# STM32_Microcontroller.net
KiCad netlist of a schematic drawn in Altium Designer
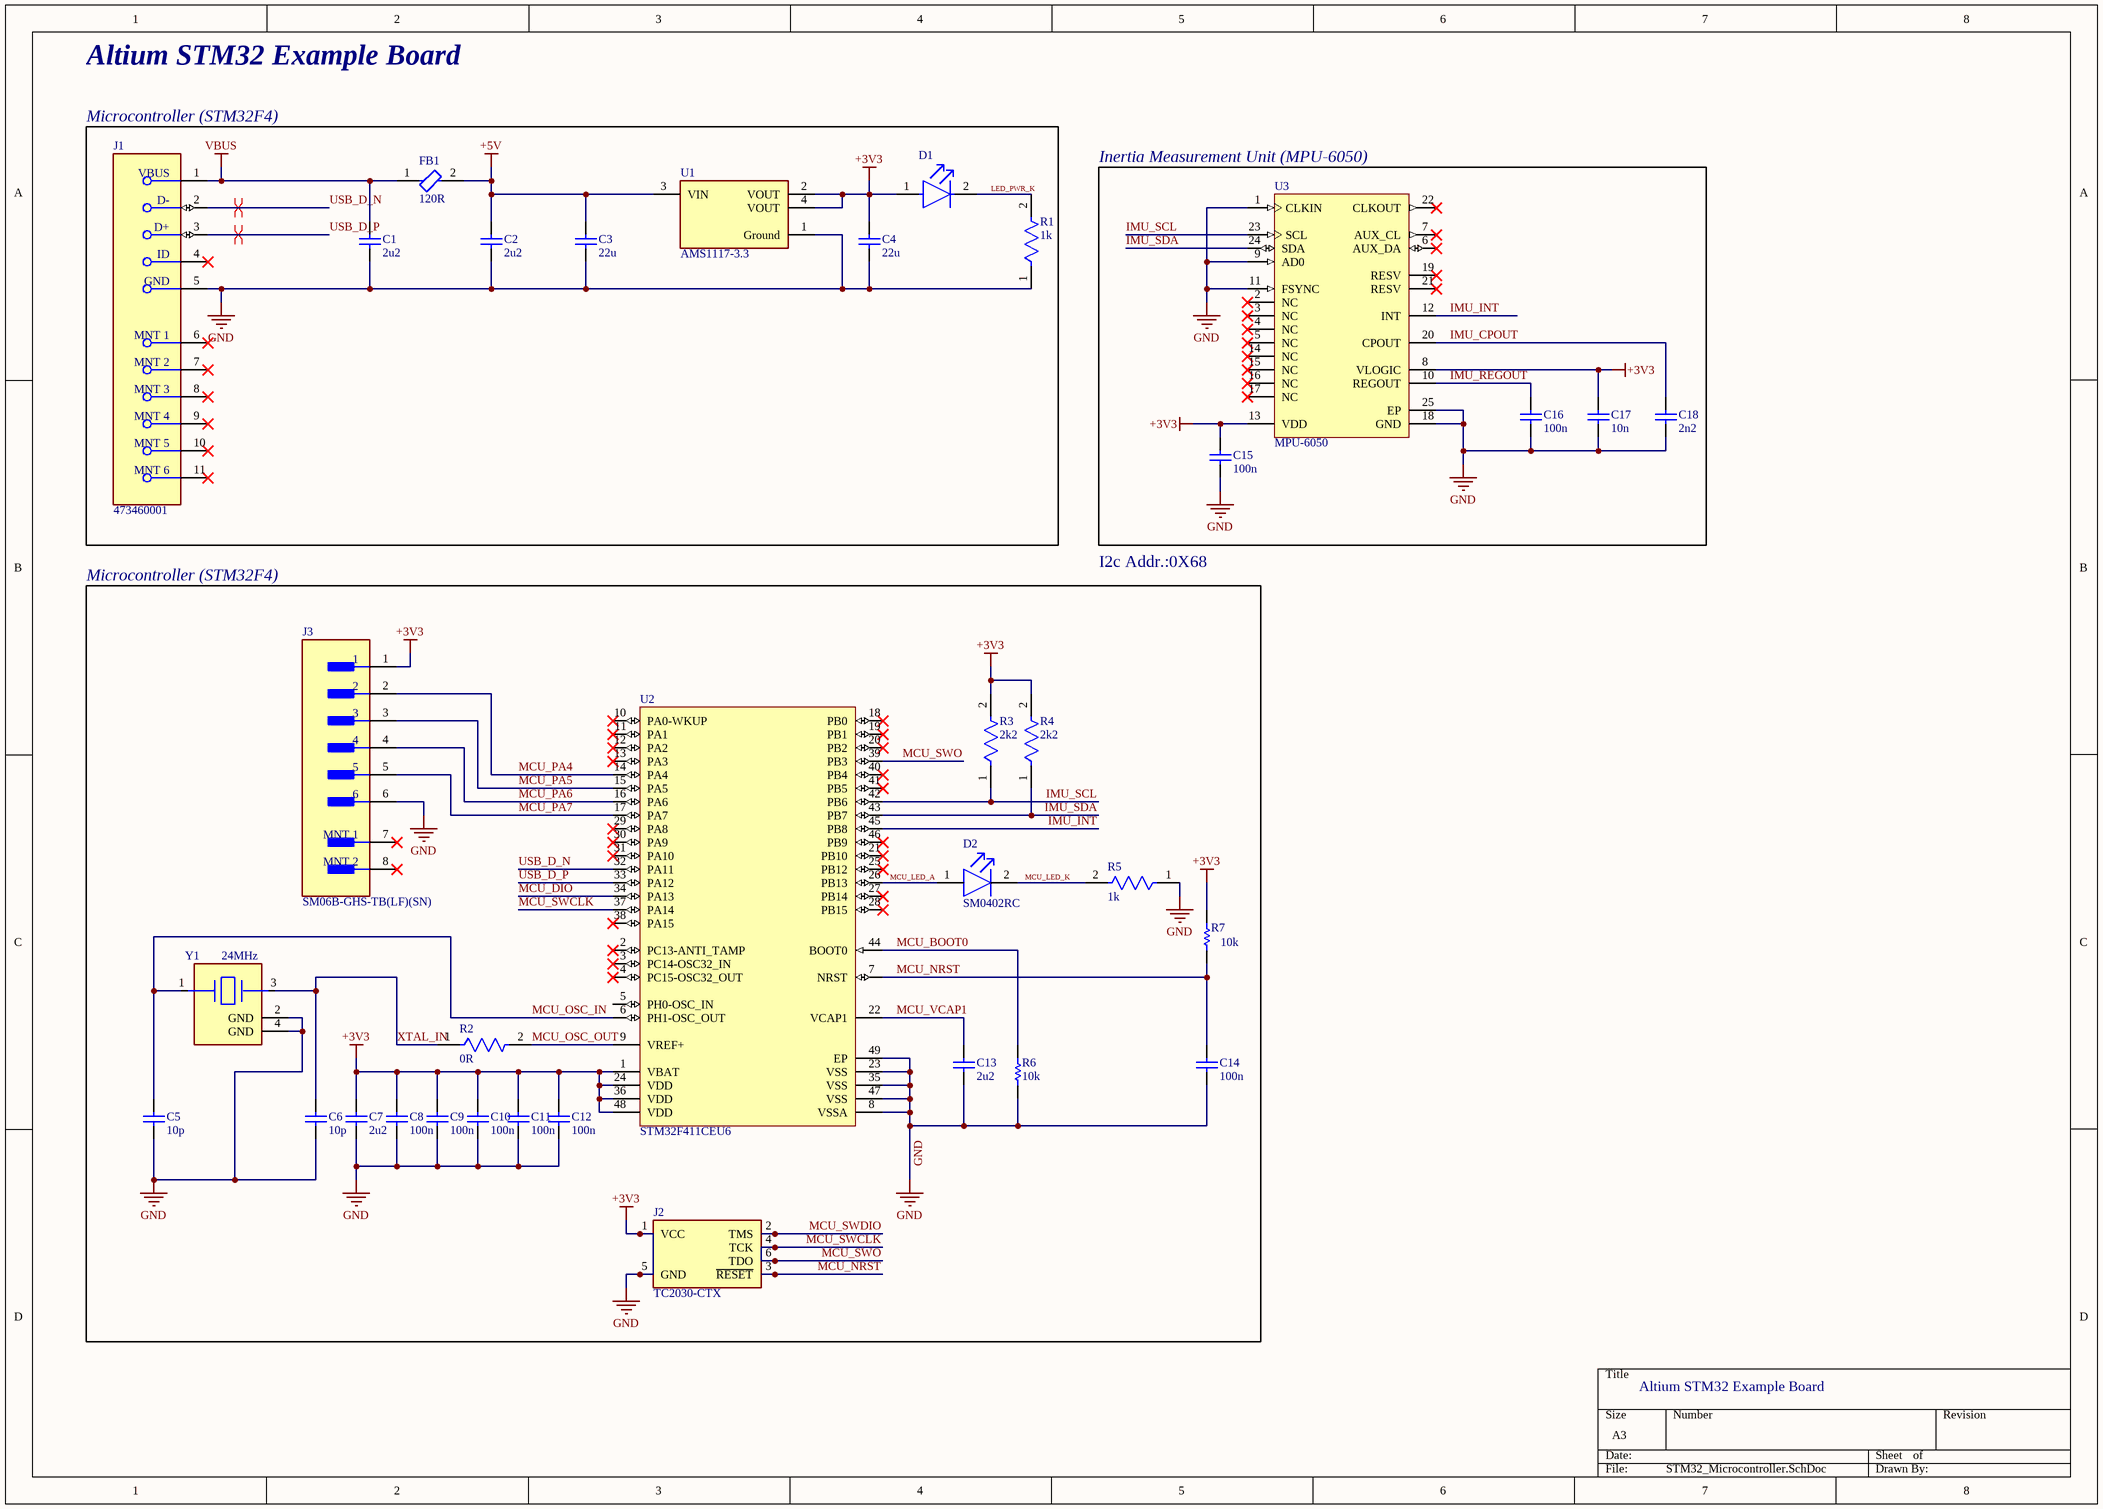
[diagram p0: STM32_Microcontroller.SchDoc]

(export (version "E")
  (design (tool "Eeschema 10.0.6"))
  (components
    (comp (ref "C1")
      (value "2u2")
      (footprint "CAPC1608X95X40ML15T15")
      (fields (field (name "PART NUMBER") "VJ0603A270JXJPW1BC") (field (name "MANUFACTURER") "Vitramon"))
      (libsource (lib "Altium Content Vault") (part "CAP"))
    )
    (comp (ref "C2")
      (value "2u2")
      (footprint "CAPC1608X95X40ML15T15")
      (fields (field (name "PART NUMBER") "VJ0603A270JXJPW1BC") (field (name "MANUFACTURER") "Vitramon"))
      (libsource (lib "Altium Content Vault") (part "CAP"))
    )
    (comp (ref "C3")
      (value "22u")
      (footprint "CAPC2013X140X50NL20T25")
      (fields (field (name "MANUFACTURER") "Kemet") (field (name "PART NUMBER") "C0805C185K4RACTU"))
      (libsource (lib "Altium Content Vault") (part "CAP"))
    )
    (comp (ref "C4")
      (value "22u")
      (footprint "CAPC2013X140X50NL20T25")
      (fields (field (name "MANUFACTURER") "Kemet") (field (name "PART NUMBER") "C0805C185K4RACTU"))
      (libsource (lib "Altium Content Vault") (part "CAP"))
    )
    (comp (ref "C5")
      (value "10p")
      (footprint "CAPC1005X60X30NL05T10")
      (fields (field (name "PART NUMBER") "C0402C103K4RALTU") (field (name "MANUFACTURER") "Kemet"))
      (libsource (lib "Altium Content Vault") (part "CAP"))
    )
    (comp (ref "C6")
      (value "10p")
      (footprint "CAPC1005X60X30NL05T10")
      (fields (field (name "PART NUMBER") "C0402C103K4RALTU") (field (name "MANUFACTURER") "Kemet"))
      (libsource (lib "Altium Content Vault") (part "CAP"))
    )
    (comp (ref "C7")
      (value "2u2")
      (footprint "CAPC1608X95X40ML15T15")
      (fields (field (name "PART NUMBER") "VJ0603A270JXJPW1BC") (field (name "MANUFACTURER") "Vitramon"))
      (libsource (lib "Altium Content Vault") (part "CAP"))
    )
    (comp (ref "C8")
      (value "100n")
      (footprint "CAPC1005X56X25LL10T15")
      (fields
        (field (name "PART NUMBER") "0402YC392KAT2A")
        (field (name "MANUFACTURER") "AVX Interconnect / Elco")
      )
      (libsource (lib "Altium Content Vault") (part "CAP"))
    )
    (comp (ref "C9")
      (value "100n")
      (footprint "CAPC1005X56X25LL10T15")
      (fields
        (field (name "PART NUMBER") "0402YC392KAT2A")
        (field (name "MANUFACTURER") "AVX Interconnect / Elco")
      )
      (libsource (lib "Altium Content Vault") (part "CAP"))
    )
    (comp (ref "C10")
      (value "100n")
      (footprint "CAPC1005X56X25LL10T15")
      (fields
        (field (name "PART NUMBER") "0402YC392KAT2A")
        (field (name "MANUFACTURER") "AVX Interconnect / Elco")
      )
      (libsource (lib "Altium Content Vault") (part "CAP"))
    )
    (comp (ref "C11")
      (value "100n")
      (footprint "CAPC1005X56X25LL10T15")
      (fields
        (field (name "PART NUMBER") "0402YC392KAT2A")
        (field (name "MANUFACTURER") "AVX Interconnect / Elco")
      )
      (libsource (lib "Altium Content Vault") (part "CAP"))
    )
    (comp (ref "C12")
      (value "100n")
      (footprint "CAPC1005X56X25LL10T15")
      (fields
        (field (name "PART NUMBER") "0402YC392KAT2A")
        (field (name "MANUFACTURER") "AVX Interconnect / Elco")
      )
      (libsource (lib "Altium Content Vault") (part "CAP"))
    )
    (comp (ref "C13")
      (value "2u2")
      (footprint "CAPC1608X95X40ML15T15")
      (fields (field (name "PART NUMBER") "VJ0603A270JXJPW1BC") (field (name "MANUFACTURER") "Vitramon"))
      (libsource (lib "Altium Content Vault") (part "CAP"))
    )
    (comp (ref "C14")
      (value "100n")
      (footprint "CAPC1005X56X25LL10T15")
      (fields
        (field (name "PART NUMBER") "0402YC392KAT2A")
        (field (name "MANUFACTURER") "AVX Interconnect / Elco")
      )
      (libsource (lib "Altium Content Vault") (part "CAP"))
    )
    (comp (ref "C15")
      (value "100n")
      (footprint "CAPC1005X56X25LL10T15")
      (fields
        (field (name "PART NUMBER") "0402YC392KAT2A")
        (field (name "MANUFACTURER") "AVX Interconnect / Elco")
      )
      (libsource (lib "Altium Content Vault") (part "CAP"))
    )
    (comp (ref "C16")
      (value "100n")
      (footprint "CAPC1005X56X25LL10T15")
      (fields
        (field (name "PART NUMBER") "0402YC392KAT2A")
        (field (name "MANUFACTURER") "AVX Interconnect / Elco")
      )
      (libsource (lib "Altium Content Vault") (part "CAP"))
    )
    (comp (ref "C17")
      (value "10n")
      (footprint "CAPC1005X56X25LL10T15")
      (fields
        (field (name "PART NUMBER") "0402YC392KAT2A")
        (field (name "MANUFACTURER") "AVX Interconnect / Elco")
      )
      (libsource (lib "Altium Content Vault") (part "CAP"))
    )
    (comp (ref "C18")
      (value "2n2")
      (footprint "CAPC1005X56X25LL10T15")
      (fields
        (field (name "PART NUMBER") "0402YC392KAT2A")
        (field (name "MANUFACTURER") "AVX Interconnect / Elco")
      )
      (libsource (lib "Altium Content Vault") (part "CAP"))
    )
    (comp (ref "D1")
      (value "SM0402GC")
      (footprint "FP-SM0402GC-MFG")
      (description "LED GREEN CLEAR 0402 SMD")
      (libsource (lib "Altium Content Vault") (part "ab1c01a81903e929fc6c44469aada92"))
    )
    (comp (ref "D2")
      (value "SM0402RC")
      (footprint "FP-SM0402RC-MFG")
      (description "LED RED CLEAR 0402 SMD")
      (libsource (lib "") (part "ab1c01a81903e929fc6c44469aada92_1"))
    )
    (comp (ref "FB1")
      (value "120R")
      (footprint "FP-BLM18-0_15-t0_8-IPC_B")
      (description "Chip Ferrite Bead, 0603, 330Ω @ 100MHz, 0.58Ω, 25%, 400mA")
      (libsource (lib "Altium Content Vault") (part "5f30dd21d616792df468990f7003faa"))
    )
    (comp (ref "J1")
      (value "473460001")
      (footprint "FP-473460001-MFG")
      (description "CONN RCPT USB2.0 MICRO B SMD R/A")
      (fields
        (field (name "OCTOPART") "https://octopart.com/47346-0001-molex-7164928")
        (field (name "MANUFACTURER") "Molex")
      )
      (libsource (lib "Altium Content Vault") (part "53ae1f1d9b557310b43ca686e5bb76a"))
    )
    (comp (ref "J2")
      (value "TC2030-CTX")
      (footprint "TC2030-IDC-NL")
      (description "CortexÂ® Plug-Of-Nailsâ„¢ Adapter Cable")
      (fields (field (name "MF") "Tag-Connect LLC"))
      (libsource (lib "TC2030-CTX") (part "TC2030-CTX"))
    )
    (comp (ref "J3")
      (value "SM06B-GHS-TB(LF)(SN)")
      (footprint "FP-SM06B-GHS-TB_LF_SN-MFG")
      (description "CONN HEADER SMD R/A 6POS 1.25MM")
      (libsource (lib "Altium Content Vault") (part "ed24c53d9ba001d1a2a686240a95171"))
    )
    (comp (ref "R1")
      (value "1k")
      (footprint "FP-RMCF0402-IPC_A")
      (description "5.1MΩ ±5% 0.063W 0402 Thick Film Chip Resistor AEC-Q200 compliant")
      (fields (field (name "TOLERANCE") "5%"))
      (libsource (lib "Altium Content Vault") (part "1029c3af85768c4190bb7ad29bc67b5"))
    )
    (comp (ref "R2")
      (value "0R")
      (footprint "FP-RMCF0402-IPC_A")
      (description "2.7MΩ ±5% 0.063W 0402 Thick Film Chip Resistor AEC-Q200 compliant")
      (fields (field (name "TOLERANCE") "5%"))
      (libsource (lib "Altium Content Vault") (part "1029c3af85768c4190bb7ad29bc67b5"))
    )
    (comp (ref "R3")
      (value "2k2")
      (footprint "FP-RMCF0402-IPC_A")
      (description "5.1MΩ ±5% 0.063W 0402 Thick Film Chip Resistor AEC-Q200 compliant")
      (fields (field (name "TOLERANCE") "5%"))
      (libsource (lib "Altium Content Vault") (part "1029c3af85768c4190bb7ad29bc67b5"))
    )
    (comp (ref "R4")
      (value "2k2")
      (footprint "FP-RMCF0402-IPC_A")
      (description "5.1MΩ ±5% 0.063W 0402 Thick Film Chip Resistor AEC-Q200 compliant")
      (fields (field (name "TOLERANCE") "5%"))
      (libsource (lib "Altium Content Vault") (part "1029c3af85768c4190bb7ad29bc67b5"))
    )
    (comp (ref "R5")
      (value "1k")
      (footprint "FP-RMCF0402-IPC_A")
      (description "5.1MΩ ±5% 0.063W 0402 Thick Film Chip Resistor AEC-Q200 compliant")
      (fields (field (name "TOLERANCE") "5%"))
      (libsource (lib "Altium Content Vault") (part "1029c3af85768c4190bb7ad29bc67b5"))
    )
    (comp (ref "R6")
      (value "10k")
      (footprint "RESC1005X40X25LL10T10")
      (fields (field (name "MANUFACTURER") "KOA Speer") (field (name "PART NUMBER") "SG73P1ETTP1002F"))
      (libsource (lib "Altium Content Vault") (part "RES"))
    )
    (comp (ref "R7")
      (value "10k")
      (footprint "RESC1005X40X25LL10T10")
      (fields (field (name "MANUFACTURER") "KOA Speer") (field (name "PART NUMBER") "SG73P1ETTP1002F"))
      (libsource (lib "Altium Content Vault") (part "RES"))
    )
    (comp (ref "U1")
      (value "AMS1117-3.3")
      (footprint "FP-AMS1117-IPC_C")
      (description "LDO Voltage Regulators 1A, 3.3V")
      (fields
        (field (name "OCTOPART") "https://octopart.com/ams1117-3.3-advanced+monolithic+systems-25899300")
        (field (name "MANUFACTURER") "Advanced Monolithic Systems")
      )
      (libsource (lib "Altium Content Vault") (part "8bdbb5f8e77002000e30dd2845d0354"))
    )
    (comp (ref "U2")
      (value "STM32F411CEU6")
      (footprint "STM-UFQFPN48_L")
      (libsource (lib "Altium Content Vault") (part "MC-ARM-STM32F411-UFQFPN48"))
    )
    (comp (ref "U3")
      (value "MPU-6050")
      (footprint "IS-QFN-24_V")
      (fields (field (name "MANUFACTURER") "InvenSense"))
      (libsource (lib "Altium Content Vault") (part "IS-MPU-6050-QFN-24"))
    )
    (comp (ref "Y1")
      (value "24MHz")
      (footprint "FP-TSX-3225-MFG")
      (description "CRYSTAL 24.0000MHZ 9PF SMD")
      (fields (field (name "TOLERANCE") "10ppm"))
      (libsource (lib "Altium Content Vault") (part "862d5228ea4a4c8f16e8fb874e464c7"))
    )
  )
  (nets
    (net (code "1") (name "+3V3") (class "Default")
      (node (ref "C1") (pin "1") (pinfunction "1_1") (pintype "passive"))
      (node (ref "C10") (pin "1") (pinfunction "1_1") (pintype "passive"))
      (node (ref "C10") (pin "2") (pinfunction "2_2") (pintype "passive"))
      (node (ref "C11") (pin "1") (pinfunction "1_1") (pintype "passive"))
      (node (ref "C11") (pin "2") (pinfunction "2_2") (pintype "passive"))
      (node (ref "C12") (pin "1") (pinfunction "1_1") (pintype "passive"))
      (node (ref "C12") (pin "2") (pinfunction "2_2") (pintype "passive"))
      (node (ref "C13") (pin "1") (pinfunction "1_1") (pintype "passive"))
      (node (ref "C14") (pin "1") (pinfunction "1_1") (pintype "passive"))
      (node (ref "C15") (pin "1") (pinfunction "1_1") (pintype "passive"))
      (node (ref "C15") (pin "2") (pinfunction "2_2") (pintype "passive"))
      (node (ref "C16") (pin "1") (pinfunction "1_1") (pintype "passive"))
      (node (ref "C17") (pin "1") (pinfunction "1_1") (pintype "passive"))
      (node (ref "C17") (pin "2") (pinfunction "2_2") (pintype "passive"))
      (node (ref "C18") (pin "2") (pinfunction "2_2") (pintype "passive"))
      (node (ref "C2") (pin "1") (pinfunction "1_1") (pintype "passive"))
      (node (ref "C3") (pin "1") (pinfunction "1_1") (pintype "passive"))
      (node (ref "C4") (pin "1") (pinfunction "1_1") (pintype "passive"))
      (node (ref "C4") (pin "2") (pinfunction "2_2") (pintype "passive"))
      (node (ref "C5") (pin "1") (pinfunction "1_1") (pintype "passive"))
      (node (ref "C6") (pin "1") (pinfunction "1_1") (pintype "passive"))
      (node (ref "C7") (pin "1") (pinfunction "1_1") (pintype "passive"))
      (node (ref "C7") (pin "2") (pinfunction "2_2") (pintype "passive"))
      (node (ref "C8") (pin "1") (pinfunction "1_1") (pintype "passive"))
      (node (ref "C8") (pin "2") (pinfunction "2_2") (pintype "passive"))
      (node (ref "C9") (pin "1") (pinfunction "1_1") (pintype "passive"))
      (node (ref "C9") (pin "2") (pinfunction "2_2") (pintype "passive"))
      (node (ref "D1") (pin "1") (pinfunction "A_1") (pintype "passive"))
      (node (ref "J1") (pin "5") (pinfunction "GND_5") (pintype "power_in"))
      (node (ref "J2") (pin "1") (pinfunction "VCC_1") (pintype "bidirectional"))
      (node (ref "J2") (pin "5") (pinfunction "GND_5") (pintype "bidirectional"))
      (node (ref "J3") (pin "1") (pinfunction "1_1") (pintype "passive"))
      (node (ref "J3") (pin "6") (pinfunction "6_6") (pintype "passive"))
      (node (ref "R1") (pin "1") (pinfunction "1_1") (pintype "passive"))
      (node (ref "R3") (pin "2") (pinfunction "2_2") (pintype "passive"))
      (node (ref "R4") (pin "2") (pinfunction "2_2") (pintype "passive"))
      (node (ref "R5") (pin "1") (pinfunction "1_1") (pintype "passive"))
      (node (ref "R6") (pin "1") (pinfunction "1_1") (pintype "passive"))
      (node (ref "R7") (pin "2") (pinfunction "2_2") (pintype "passive"))
      (node (ref "U1") (pin "1") (pinfunction "Ground_1") (pintype "power_in"))
      (node (ref "U1") (pin "2") (pinfunction "VOUT_2") (pintype "passive"))
      (node (ref "U1") (pin "4") (pinfunction "VOUT_4") (pintype "passive"))
      (node (ref "U2") (pin "1") (pinfunction "VBAT_1") (pintype "power_in"))
      (node (ref "U2") (pin "23") (pinfunction "VSS_23") (pintype "power_in"))
      (node (ref "U2") (pin "24") (pinfunction "VDD_24") (pintype "power_in"))
      (node (ref "U2") (pin "35") (pinfunction "VSS_35") (pintype "power_in"))
      (node (ref "U2") (pin "36") (pinfunction "VDD_36") (pintype "power_in"))
      (node (ref "U2") (pin "47") (pinfunction "VSS_47") (pintype "power_in"))
      (node (ref "U2") (pin "48") (pinfunction "VDD_48") (pintype "power_in"))
      (node (ref "U2") (pin "49") (pinfunction "EP_49") (pintype "power_in"))
      (node (ref "U2") (pin "8") (pinfunction "VSSA_8") (pintype "power_in"))
      (node (ref "U3") (pin "1") (pinfunction "CLKIN_1") (pintype "input"))
      (node (ref "U3") (pin "11") (pinfunction "FSYNC_11") (pintype "input"))
      (node (ref "U3") (pin "13") (pinfunction "VDD_13") (pintype "power_in"))
      (node (ref "U3") (pin "18") (pinfunction "GND_18") (pintype "power_in"))
      (node (ref "U3") (pin "25") (pinfunction "EP_25") (pintype "power_in"))
      (node (ref "U3") (pin "8") (pinfunction "VLOGIC_8") (pintype "power_in"))
      (node (ref "U3") (pin "9") (pinfunction "AD0_9") (pintype "input"))
      (node (ref "Y1") (pin "2") (pinfunction "GND_2") (pintype "power_in"))
      (node (ref "Y1") (pin "4") (pinfunction "GND_4") (pintype "power_in"))
    )
    (net (code "2") (name "+5V") (class "Default")
      (node (ref "C2") (pin "2") (pinfunction "2_2") (pintype "passive"))
      (node (ref "C3") (pin "2") (pinfunction "2_2") (pintype "passive"))
      (node (ref "FB1") (pin "2") (pinfunction "2_2") (pintype "passive"))
      (node (ref "U1") (pin "3") (pinfunction "VIN_3") (pintype "power_in"))
    )
    (net (code "3") (name "/IMU_CPOUT") (class "Default")
      (node (ref "C18") (pin "1") (pinfunction "1_1") (pintype "passive"))
      (node (ref "U3") (pin "20") (pinfunction "CPOUT_20") (pintype "passive"))
    )
    (net (code "4") (name "/IMU_INT") (class "Default")
      (node (ref "U2") (pin "45") (pinfunction "PB8_45") (pintype "bidirectional"))
      (node (ref "U3") (pin "12") (pinfunction "INT_12") (pintype "open_collector"))
    )
    (net (code "5") (name "/IMU_REGOUT") (class "Default")
      (node (ref "C16") (pin "2") (pinfunction "2_2") (pintype "passive"))
      (node (ref "U3") (pin "10") (pinfunction "REGOUT_10") (pintype "passive"))
    )
    (net (code "6") (name "/IMU_SCL") (class "Default")
      (node (ref "R3") (pin "1") (pinfunction "1_1") (pintype "passive"))
      (node (ref "U2") (pin "42") (pinfunction "PB6_42") (pintype "bidirectional"))
      (node (ref "U3") (pin "23") (pinfunction "SCL_23") (pintype "input"))
    )
    (net (code "7") (name "/IMU_SDA") (class "Default")
      (node (ref "R4") (pin "1") (pinfunction "1_1") (pintype "passive"))
      (node (ref "U2") (pin "43") (pinfunction "PB7_43") (pintype "bidirectional"))
      (node (ref "U3") (pin "24") (pinfunction "SDA_24") (pintype "bidirectional"))
    )
    (net (code "8") (name "/LED_PWR_K") (class "Default")
      (node (ref "D1") (pin "2") (pinfunction "C_2") (pintype "passive"))
      (node (ref "R1") (pin "2") (pinfunction "2_2") (pintype "passive"))
    )
    (net (code "9") (name "/MCU_BOOT0") (class "Default")
      (node (ref "R6") (pin "2") (pinfunction "2_2") (pintype "passive"))
      (node (ref "U2") (pin "44") (pinfunction "BOOT0_44") (pintype "input"))
    )
    (net (code "10") (name "/MCU_DIO") (class "Default")
      (node (ref "U2") (pin "34") (pinfunction "PA13_34") (pintype "bidirectional"))
    )
    (net (code "11") (name "/MCU_LED_A") (class "Default")
      (node (ref "D2") (pin "1") (pinfunction "A_1") (pintype "passive"))
      (node (ref "U2") (pin "26") (pinfunction "PB13_26") (pintype "bidirectional"))
    )
    (net (code "12") (name "/MCU_LED_K") (class "Default")
      (node (ref "D2") (pin "2") (pinfunction "C_2") (pintype "passive"))
      (node (ref "R5") (pin "2") (pinfunction "2_2") (pintype "passive"))
    )
    (net (code "13") (name "/MCU_NRST") (class "Default")
      (node (ref "C14") (pin "2") (pinfunction "2_2") (pintype "passive"))
      (node (ref "J2") (pin "3") (pinfunction "~{RESET}_3") (pintype "bidirectional"))
      (node (ref "R7") (pin "1") (pinfunction "1_1") (pintype "passive"))
      (node (ref "U2") (pin "7") (pinfunction "NRST_7") (pintype "bidirectional"))
    )
    (net (code "14") (name "/MCU_OSC_IN") (class "Default")
      (node (ref "C5") (pin "2") (pinfunction "2_2") (pintype "passive"))
      (node (ref "U2") (pin "6") (pinfunction "PH1-OSC_OUT_6") (pintype "bidirectional"))
      (node (ref "Y1") (pin "1") (pinfunction "1_1") (pintype "passive"))
    )
    (net (code "15") (name "/MCU_OSC_OUT") (class "Default")
      (node (ref "R2") (pin "2") (pinfunction "2_2") (pintype "passive"))
      (node (ref "U2") (pin "9") (pinfunction "VREF+_9") (pintype "power_in"))
    )
    (net (code "16") (name "/MCU_PA4") (class "Default")
      (node (ref "J3") (pin "2") (pinfunction "2_2") (pintype "passive"))
      (node (ref "U2") (pin "14") (pinfunction "PA4_14") (pintype "bidirectional"))
    )
    (net (code "17") (name "/MCU_PA5") (class "Default")
      (node (ref "J3") (pin "3") (pinfunction "3_3") (pintype "passive"))
      (node (ref "U2") (pin "15") (pinfunction "PA5_15") (pintype "bidirectional"))
    )
    (net (code "18") (name "/MCU_PA6") (class "Default")
      (node (ref "J3") (pin "4") (pinfunction "4_4") (pintype "passive"))
      (node (ref "U2") (pin "16") (pinfunction "PA6_16") (pintype "bidirectional"))
    )
    (net (code "19") (name "/MCU_PA7") (class "Default")
      (node (ref "J3") (pin "5") (pinfunction "5_5") (pintype "passive"))
      (node (ref "U2") (pin "17") (pinfunction "PA7_17") (pintype "bidirectional"))
    )
    (net (code "20") (name "/MCU_SWCLK") (class "Default")
      (node (ref "J2") (pin "4") (pinfunction "TCK_4") (pintype "bidirectional"))
      (node (ref "J2") (pin "6") (pinfunction "TDO_6") (pintype "bidirectional"))
      (node (ref "U2") (pin "37") (pinfunction "PA14_37") (pintype "bidirectional"))
      (node (ref "U2") (pin "39") (pinfunction "PB3_39") (pintype "bidirectional"))
    )
    (net (code "21") (name "/MCU_SWDIO") (class "Default")
      (node (ref "J2") (pin "2") (pinfunction "TMS_2") (pintype "bidirectional"))
    )
    (net (code "22") (name "/MCU_VCAP1") (class "Default")
      (node (ref "C13") (pin "2") (pinfunction "2_2") (pintype "passive"))
      (node (ref "U2") (pin "22") (pinfunction "VCAP1_22") (pintype "passive"))
    )
    (net (code "23") (name "/USB_D_N") (class "Default")
      (node (ref "J1") (pin "2") (pinfunction "D-_2") (pintype "bidirectional"))
      (node (ref "U2") (pin "32") (pinfunction "PA11_32") (pintype "bidirectional"))
    )
    (net (code "24") (name "/USB_D_P") (class "Default")
      (node (ref "J1") (pin "3") (pinfunction "D+_3") (pintype "bidirectional"))
      (node (ref "U2") (pin "33") (pinfunction "PA12_33") (pintype "bidirectional"))
    )
    (net (code "25") (name "/XTAL_IN") (class "Default")
      (node (ref "C6") (pin "2") (pinfunction "2_2") (pintype "passive"))
      (node (ref "R2") (pin "1") (pinfunction "1_1") (pintype "passive"))
      (node (ref "Y1") (pin "3") (pinfunction "3_3") (pintype "passive"))
    )
    (net (code "26") (name "VBUS") (class "Default")
      (node (ref "C1") (pin "2") (pinfunction "2_2") (pintype "passive"))
      (node (ref "FB1") (pin "1") (pinfunction "1_1") (pintype "passive"))
      (node (ref "J1") (pin "1") (pinfunction "VBUS_1") (pintype "power_in"))
    )
    (net (code "27") (name "unconnected-(J1-ID-Pad4)") (class "Default")
      (node (ref "J1") (pin "4") (pinfunction "ID_4") (pintype "passive+no_connect"))
    )
    (net (code "28") (name "unconnected-(J1-MNT_1-Pad6)") (class "Default")
      (node (ref "J1") (pin "6") (pinfunction "MNT_1_6") (pintype "passive+no_connect"))
    )
    (net (code "29") (name "unconnected-(J1-MNT_2-Pad7)") (class "Default")
      (node (ref "J1") (pin "7") (pinfunction "MNT_2_7") (pintype "passive+no_connect"))
    )
    (net (code "30") (name "unconnected-(J1-MNT_3-Pad8)") (class "Default")
      (node (ref "J1") (pin "8") (pinfunction "MNT_3_8") (pintype "passive+no_connect"))
    )
    (net (code "31") (name "unconnected-(J1-MNT_4-Pad9)") (class "Default")
      (node (ref "J1") (pin "9") (pinfunction "MNT_4_9") (pintype "passive+no_connect"))
    )
    (net (code "32") (name "unconnected-(J1-MNT_5-Pad10)") (class "Default")
      (node (ref "J1") (pin "10") (pinfunction "MNT_5_10") (pintype "passive+no_connect"))
    )
    (net (code "33") (name "unconnected-(J1-MNT_6-Pad11)") (class "Default")
      (node (ref "J1") (pin "11") (pinfunction "MNT_6_11") (pintype "passive+no_connect"))
    )
    (net (code "34") (name "unconnected-(J3-MNT_1-Pad7)") (class "Default")
      (node (ref "J3") (pin "7") (pinfunction "MNT_1_7") (pintype "passive+no_connect"))
    )
    (net (code "35") (name "unconnected-(J3-MNT_2-Pad8)") (class "Default")
      (node (ref "J3") (pin "8") (pinfunction "MNT_2_8") (pintype "passive+no_connect"))
    )
    (net (code "36") (name "unconnected-(U2-PA0-WKUP-Pad10)") (class "Default")
      (node (ref "U2") (pin "10") (pinfunction "PA0-WKUP_10") (pintype "bidirectional+no_connect"))
    )
    (net (code "37") (name "unconnected-(U2-PA1-Pad11)") (class "Default")
      (node (ref "U2") (pin "11") (pinfunction "PA1_11") (pintype "bidirectional+no_connect"))
    )
    (net (code "38") (name "unconnected-(U2-PA2-Pad12)") (class "Default")
      (node (ref "U2") (pin "12") (pinfunction "PA2_12") (pintype "bidirectional+no_connect"))
    )
    (net (code "39") (name "unconnected-(U2-PA3-Pad13)") (class "Default")
      (node (ref "U2") (pin "13") (pinfunction "PA3_13") (pintype "bidirectional+no_connect"))
    )
    (net (code "40") (name "unconnected-(U2-PA8-Pad29)") (class "Default")
      (node (ref "U2") (pin "29") (pinfunction "PA8_29") (pintype "bidirectional+no_connect"))
    )
    (net (code "41") (name "unconnected-(U2-PA9-Pad30)") (class "Default")
      (node (ref "U2") (pin "30") (pinfunction "PA9_30") (pintype "bidirectional+no_connect"))
    )
    (net (code "42") (name "unconnected-(U2-PA10-Pad31)") (class "Default")
      (node (ref "U2") (pin "31") (pinfunction "PA10_31") (pintype "bidirectional+no_connect"))
    )
    (net (code "43") (name "unconnected-(U2-PA15-Pad38)") (class "Default")
      (node (ref "U2") (pin "38") (pinfunction "PA15_38") (pintype "bidirectional+no_connect"))
    )
    (net (code "44") (name "unconnected-(U2-PB0-Pad18)") (class "Default")
      (node (ref "U2") (pin "18") (pinfunction "PB0_18") (pintype "bidirectional+no_connect"))
    )
    (net (code "45") (name "unconnected-(U2-PB1-Pad19)") (class "Default")
      (node (ref "U2") (pin "19") (pinfunction "PB1_19") (pintype "bidirectional+no_connect"))
    )
    (net (code "46") (name "unconnected-(U2-PB2-Pad20)") (class "Default")
      (node (ref "U2") (pin "20") (pinfunction "PB2_20") (pintype "bidirectional+no_connect"))
    )
    (net (code "47") (name "unconnected-(U2-PB4-Pad40)") (class "Default")
      (node (ref "U2") (pin "40") (pinfunction "PB4_40") (pintype "bidirectional+no_connect"))
    )
    (net (code "48") (name "unconnected-(U2-PB5-Pad41)") (class "Default")
      (node (ref "U2") (pin "41") (pinfunction "PB5_41") (pintype "bidirectional+no_connect"))
    )
    (net (code "49") (name "unconnected-(U2-PB9-Pad46)") (class "Default")
      (node (ref "U2") (pin "46") (pinfunction "PB9_46") (pintype "bidirectional+no_connect"))
    )
    (net (code "50") (name "unconnected-(U2-PB10-Pad21)") (class "Default")
      (node (ref "U2") (pin "21") (pinfunction "PB10_21") (pintype "bidirectional+no_connect"))
    )
    (net (code "51") (name "unconnected-(U2-PB12-Pad25)") (class "Default")
      (node (ref "U2") (pin "25") (pinfunction "PB12_25") (pintype "bidirectional+no_connect"))
    )
    (net (code "52") (name "unconnected-(U2-PB14-Pad27)") (class "Default")
      (node (ref "U2") (pin "27") (pinfunction "PB14_27") (pintype "bidirectional+no_connect"))
    )
    (net (code "53") (name "unconnected-(U2-PB15-Pad28)") (class "Default")
      (node (ref "U2") (pin "28") (pinfunction "PB15_28") (pintype "bidirectional+no_connect"))
    )
    (net (code "54") (name "unconnected-(U2-PC13-ANTI_TAMP-Pad2)") (class "Default")
      (node (ref "U2") (pin "2") (pinfunction "PC13-ANTI_TAMP_2") (pintype "bidirectional+no_connect"))
    )
    (net (code "55") (name "unconnected-(U2-PC14-OSC32_IN-Pad3)") (class "Default")
      (node (ref "U2") (pin "3") (pinfunction "PC14-OSC32_IN_3") (pintype "bidirectional+no_connect"))
    )
    (net (code "56") (name "unconnected-(U2-PC15-OSC32_OUT-Pad4)") (class "Default")
      (node (ref "U2") (pin "4") (pinfunction "PC15-OSC32_OUT_4") (pintype "bidirectional+no_connect"))
    )
    (net (code "57") (name "unconnected-(U2-PH0-OSC_IN-Pad5)") (class "Default")
      (node (ref "U2") (pin "5") (pinfunction "PH0-OSC_IN_5") (pintype "bidirectional"))
    )
    (net (code "58") (name "unconnected-(U3-AUX_CL-Pad7)") (class "Default")
      (node (ref "U3") (pin "7") (pinfunction "AUX_CL_7") (pintype "output+no_connect"))
    )
    (net (code "59") (name "unconnected-(U3-AUX_DA-Pad6)") (class "Default")
      (node (ref "U3") (pin "6") (pinfunction "AUX_DA_6") (pintype "bidirectional+no_connect"))
    )
    (net (code "60") (name "unconnected-(U3-CLKOUT-Pad22)") (class "Default")
      (node (ref "U3") (pin "22") (pinfunction "CLKOUT_22") (pintype "output+no_connect"))
    )
    (net (code "61") (name "unconnected-(U3-NC-Pad2)") (class "Default")
      (node (ref "U3") (pin "2") (pinfunction "NC_2") (pintype "passive+no_connect"))
    )
    (net (code "62") (name "unconnected-(U3-NC-Pad3)") (class "Default")
      (node (ref "U3") (pin "3") (pinfunction "NC_3") (pintype "passive+no_connect"))
    )
    (net (code "63") (name "unconnected-(U3-NC-Pad4)") (class "Default")
      (node (ref "U3") (pin "4") (pinfunction "NC_4") (pintype "passive+no_connect"))
    )
    (net (code "64") (name "unconnected-(U3-NC-Pad5)") (class "Default")
      (node (ref "U3") (pin "5") (pinfunction "NC_5") (pintype "passive+no_connect"))
    )
    (net (code "65") (name "unconnected-(U3-NC-Pad14)") (class "Default")
      (node (ref "U3") (pin "14") (pinfunction "NC_14") (pintype "passive+no_connect"))
    )
    (net (code "66") (name "unconnected-(U3-NC-Pad15)") (class "Default")
      (node (ref "U3") (pin "15") (pinfunction "NC_15") (pintype "passive+no_connect"))
    )
    (net (code "67") (name "unconnected-(U3-NC-Pad16)") (class "Default")
      (node (ref "U3") (pin "16") (pinfunction "NC_16") (pintype "passive+no_connect"))
    )
    (net (code "68") (name "unconnected-(U3-NC-Pad17)") (class "Default")
      (node (ref "U3") (pin "17") (pinfunction "NC_17") (pintype "passive+no_connect"))
    )
    (net (code "69") (name "unconnected-(U3-RESV-Pad19)") (class "Default")
      (node (ref "U3") (pin "19") (pinfunction "RESV_19") (pintype "passive+no_connect"))
    )
    (net (code "70") (name "unconnected-(U3-RESV-Pad21)") (class "Default")
      (node (ref "U3") (pin "21") (pinfunction "RESV_21") (pintype "passive+no_connect"))
    )
  )
)
